# 9_Fan.net
KiCad netlist of a schematic drawn in Altium Designer
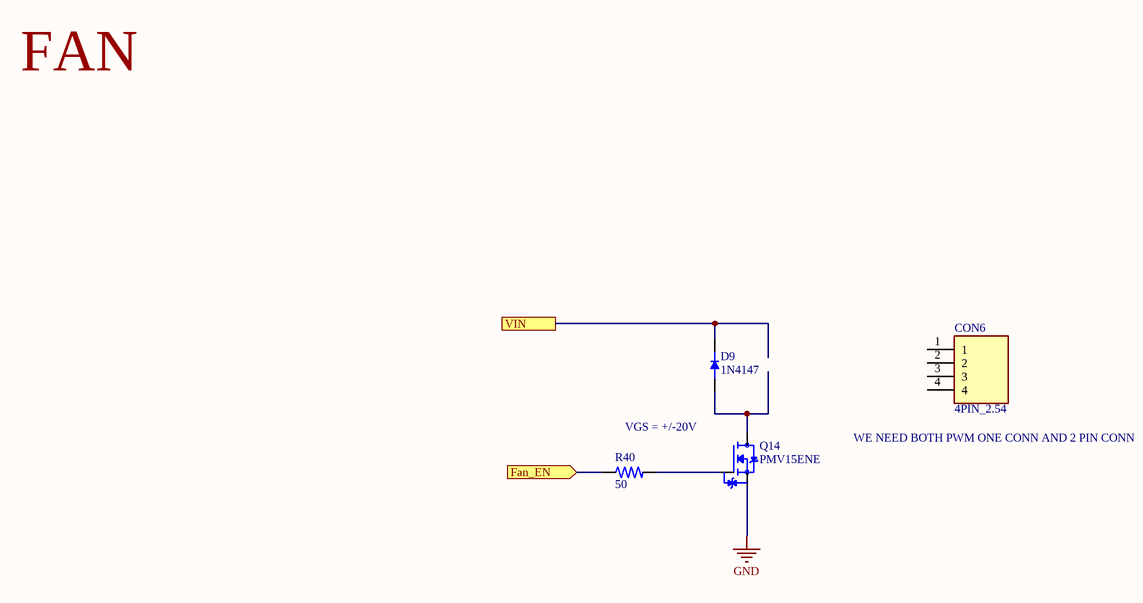
[diagram p0: 9.Fan.SchDoc]

(export (version "E")
  (design (tool "Eeschema 10.0.6"))
  (components
    (comp (ref "CON6")
      (value "4PIN_2.54")
      (footprint "PcbLib:4Pin_2.5")
      (libsource (lib "Schlib") (part "4PIN_2.54"))
    )
    (comp (ref "D9")
      (value "1N4147")
      (footprint "SOD123")
      (fields (field (name "MFR") "Panjit"))
      (libsource (lib "Schlib") (part "1N4147"))
    )
    (comp (ref "Q14")
      (value "PMV15ENE")
      (footprint "SOT23FR")
      (fields (field (name "MFR") "Nexperia"))
      (libsource (lib "Schlib") (part "PMV15ENE"))
    )
    (comp (ref "R40") (value "50") (footprint "R_0603") (libsource (lib "Schlib") (part "R_0603")))
  )
  (nets
    (net (code "1") (name "/Fan_EN") (class "Default")
      (node (ref "R40") (pin "1") (pinfunction "1_1") (pintype "passive"))
    )
    (net (code "2") (name "/VIN") (class "Default")
      (node (ref "D9") (pin "C") (pinfunction "K_C") (pintype "passive"))
    )
    (net (code "3") (name "GND") (class "Default")
      (node (ref "Q14") (pin "3") (pinfunction "S_3") (pintype "passive"))
    )
    (net (code "4") (name "Net-(Q14-D)") (class "Default")
      (node (ref "D9") (pin "A") (pinfunction "A_A") (pintype "passive"))
      (node (ref "Q14") (pin "1") (pinfunction "D_1") (pintype "passive"))
    )
    (net (code "5") (name "Net-(Q14-G)") (class "Default")
      (node (ref "Q14") (pin "2") (pinfunction "G_2") (pintype "passive"))
      (node (ref "R40") (pin "2") (pinfunction "2_2") (pintype "passive"))
    )
    (net (code "6") (name "unconnected-(CON6-Pad1)") (class "Default")
      (node (ref "CON6") (pin "1") (pinfunction "1_1") (pintype "passive"))
    )
    (net (code "7") (name "unconnected-(CON6-Pad2)") (class "Default")
      (node (ref "CON6") (pin "2") (pinfunction "2_2") (pintype "passive"))
    )
    (net (code "8") (name "unconnected-(CON6-Pad3)") (class "Default")
      (node (ref "CON6") (pin "3") (pinfunction "3_3") (pintype "passive"))
    )
    (net (code "9") (name "unconnected-(CON6-Pad4)") (class "Default")
      (node (ref "CON6") (pin "4") (pinfunction "4_4") (pintype "passive"))
    )
  )
)
